# RFM6505B.net
KiCad netlist of a schematic drawn in Altium Designer
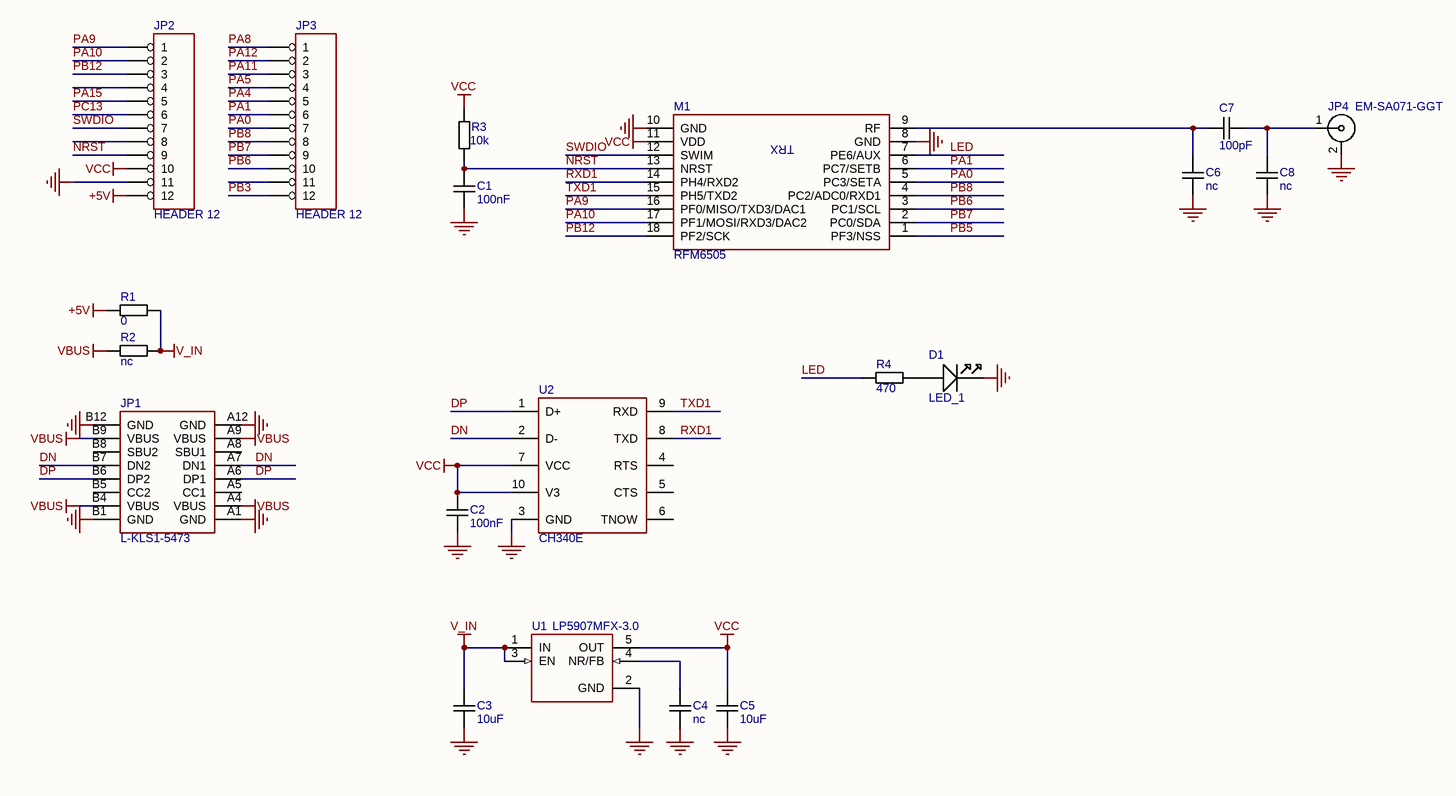
[diagram p0: RFM6505B.SchDoc]

(export (version "E")
  (design (tool "Eeschema 10.0.6"))
  (components
    (comp (ref "C1")
      (value "100nF")
      (footprint "C-0603")
      (fields (field (name "VOLTAGE") "50V"))
      (libsource (lib "Passive") (part "CAPN"))
    )
    (comp (ref "C2")
      (value "100nF")
      (footprint "C-0603")
      (fields (field (name "VOLTAGE") "50V"))
      (libsource (lib "Passive") (part "CAPN"))
    )
    (comp (ref "C3")
      (value "10uF")
      (footprint "C-0805")
      (fields (field (name "VOLTAGE") "50V"))
      (libsource (lib "Passive") (part "CAPN"))
    )
    (comp (ref "C4")
      (value "nc")
      (footprint "C-0603")
      (fields (field (name "VOLTAGE") "50V"))
      (libsource (lib "Passive") (part "CAPN"))
    )
    (comp (ref "C5")
      (value "10uF")
      (footprint "C-0805")
      (fields (field (name "VOLTAGE") "50V"))
      (libsource (lib "Passive") (part "CAPN"))
    )
    (comp (ref "C6")
      (value "nc")
      (footprint "C-0603")
      (fields (field (name "VOLTAGE") "50V"))
      (libsource (lib "Passive") (part "CAPN"))
    )
    (comp (ref "C7")
      (value "100pF")
      (footprint "C-0603")
      (fields (field (name "VOLTAGE") "50V"))
      (libsource (lib "Passive") (part "CAPN"))
    )
    (comp (ref "C8")
      (value "nc")
      (footprint "C-0603")
      (fields (field (name "VOLTAGE") "50V"))
      (libsource (lib "Passive") (part "CAPN"))
    )
    (comp (ref "D1") (value "LED_1") (footprint "LED_0805") (libsource (lib "Diodes") (part "LED_1")))
    (comp (ref "JP1")
      (value "L-KLS1-5473")
      (footprint "USB_C_SMD_SLOT")
      (libsource (lib "Connectors") (part "L-KLS1-5473"))
    )
    (comp (ref "JP2")
      (value "HEADER 12")
      (footprint "PLS1-12")
      (libsource (lib "Connectors") (part "HEADER 12"))
    )
    (comp (ref "JP3")
      (value "HEADER 12")
      (footprint "PLS1-12")
      (libsource (lib "Connectors") (part "HEADER 12"))
    )
    (comp (ref "JP4")
      (value "EM-SA071-GGT")
      (footprint "SMA_F_EDGE")
      (description "SMA Female R/A PCB Mount")
      (libsource (lib "Connectors") (part "SMA"))
    )
    (comp (ref "M1") (value "RFM6505") (footprint "RFM6505") (libsource (lib "RFmodules") (part "RFM6505")))
    (comp (ref "R1") (value "0") (footprint "R-0603") (libsource (lib "Passive") (part "RES")))
    (comp (ref "R2") (value "nc") (footprint "R-0603") (libsource (lib "Passive") (part "RES")))
    (comp (ref "R3") (value "10k") (footprint "R-0603") (libsource (lib "") (part "RES_1")))
    (comp (ref "R4") (value "470") (footprint "R-0603") (libsource (lib "") (part "RES_2")))
    (comp (ref "U1")
      (value "LP5907MFX-3.0")
      (footprint "SOT-23-5")
      (description "250mA Low-Dropout Regulator")
      (libsource (lib "ICs") (part "LP5907"))
    )
    (comp (ref "U2") (value "CH340E") (footprint "MSOP-10") (libsource (lib "ICs") (part "CH340E")))
  )
  (nets
    (net (code "1") (name "+5V") (class "Default")
      (node (ref "JP2") (pin "12") (pinfunction "12_12") (pintype "passive"))
      (node (ref "R1") (pin "1") (pinfunction "1_1") (pintype "passive"))
    )
    (net (code "2") (name "/DN") (class "Default")
      (node (ref "JP1") (pin "A7") (pinfunction "DN1_A7") (pintype "passive"))
      (node (ref "JP1") (pin "B7") (pinfunction "DN2_B7") (pintype "passive"))
      (node (ref "U2") (pin "2") (pinfunction "D-_2") (pintype "passive"))
    )
    (net (code "3") (name "/DP") (class "Default")
      (node (ref "JP1") (pin "A6") (pinfunction "DP1_A6") (pintype "passive"))
      (node (ref "JP1") (pin "B6") (pinfunction "DP2_B6") (pintype "passive"))
      (node (ref "U2") (pin "1") (pinfunction "D+_1") (pintype "passive"))
    )
    (net (code "4") (name "/LED") (class "Default")
      (node (ref "M1") (pin "7") (pinfunction "PE6/AUX_7") (pintype "passive"))
      (node (ref "R4") (pin "2") (pinfunction "2_2") (pintype "passive"))
    )
    (net (code "5") (name "/NRST") (class "Default")
      (node (ref "C1") (pin "2") (pinfunction "2_2") (pintype "passive"))
      (node (ref "JP2") (pin "9") (pinfunction "9_9") (pintype "passive"))
      (node (ref "M1") (pin "13") (pinfunction "NRST_13") (pintype "passive"))
      (node (ref "R3") (pin "1") (pinfunction "1_1") (pintype "passive"))
    )
    (net (code "6") (name "/PA0") (class "Default")
      (node (ref "JP3") (pin "7") (pinfunction "7_7") (pintype "passive"))
      (node (ref "M1") (pin "5") (pinfunction "PC3/SETA_5") (pintype "passive"))
    )
    (net (code "7") (name "/PA1") (class "Default")
      (node (ref "JP3") (pin "6") (pinfunction "6_6") (pintype "passive"))
      (node (ref "M1") (pin "6") (pinfunction "PC7/SETB_6") (pintype "passive"))
    )
    (net (code "8") (name "/PA4") (class "Default")
      (node (ref "JP3") (pin "5") (pinfunction "5_5") (pintype "passive"))
    )
    (net (code "9") (name "/PA5") (class "Default")
      (node (ref "JP3") (pin "4") (pinfunction "4_4") (pintype "passive"))
    )
    (net (code "10") (name "/PA8") (class "Default")
      (node (ref "JP3") (pin "1") (pinfunction "1_1") (pintype "passive"))
    )
    (net (code "11") (name "/PA9") (class "Default")
      (node (ref "JP2") (pin "1") (pinfunction "1_1") (pintype "passive"))
      (node (ref "M1") (pin "16") (pinfunction "PF0/MISO/TXD3/DAC1_16") (pintype "passive"))
    )
    (net (code "12") (name "/PA10") (class "Default")
      (node (ref "JP2") (pin "2") (pinfunction "2_2") (pintype "passive"))
      (node (ref "M1") (pin "17") (pinfunction "PF1/MOSI/RXD3/DAC2_17") (pintype "passive"))
    )
    (net (code "13") (name "/PA11") (class "Default")
      (node (ref "JP3") (pin "3") (pinfunction "3_3") (pintype "passive"))
    )
    (net (code "14") (name "/PA12") (class "Default")
      (node (ref "JP3") (pin "2") (pinfunction "2_2") (pintype "passive"))
    )
    (net (code "15") (name "/PA15") (class "Default")
      (node (ref "JP2") (pin "5") (pinfunction "5_5") (pintype "passive"))
    )
    (net (code "16") (name "/PB3") (class "Default")
      (node (ref "JP3") (pin "12") (pinfunction "12_12") (pintype "passive"))
    )
    (net (code "17") (name "/PB5") (class "Default")
      (node (ref "M1") (pin "1") (pinfunction "PF3/NSS_1") (pintype "passive"))
    )
    (net (code "18") (name "/PB6") (class "Default")
      (node (ref "JP3") (pin "10") (pinfunction "10_10") (pintype "passive"))
      (node (ref "M1") (pin "3") (pinfunction "PC1/SCL_3") (pintype "passive"))
    )
    (net (code "19") (name "/PB7") (class "Default")
      (node (ref "JP3") (pin "9") (pinfunction "9_9") (pintype "passive"))
      (node (ref "M1") (pin "2") (pinfunction "PC0/SDA_2") (pintype "passive"))
    )
    (net (code "20") (name "/PB8") (class "Default")
      (node (ref "JP3") (pin "8") (pinfunction "8_8") (pintype "passive"))
      (node (ref "M1") (pin "4") (pinfunction "PC2/ADC0/RXD1_4") (pintype "passive"))
    )
    (net (code "21") (name "/PB12") (class "Default")
      (node (ref "JP2") (pin "3") (pinfunction "3_3") (pintype "passive"))
      (node (ref "M1") (pin "18") (pinfunction "PF2/SCK_18") (pintype "passive"))
    )
    (net (code "22") (name "/PC13") (class "Default")
      (node (ref "JP2") (pin "6") (pinfunction "6_6") (pintype "passive"))
    )
    (net (code "23") (name "/RXD1") (class "Default")
      (node (ref "M1") (pin "14") (pinfunction "PH4/RXD2_14") (pintype "passive"))
      (node (ref "U2") (pin "8") (pinfunction "TXD_8") (pintype "passive"))
    )
    (net (code "24") (name "/SWDIO") (class "Default")
      (node (ref "JP2") (pin "7") (pinfunction "7_7") (pintype "passive"))
      (node (ref "M1") (pin "12") (pinfunction "SWIM_12") (pintype "passive"))
    )
    (net (code "25") (name "/TXD1") (class "Default")
      (node (ref "M1") (pin "15") (pinfunction "PH5/TXD2_15") (pintype "passive"))
      (node (ref "U2") (pin "9") (pinfunction "RXD_9") (pintype "passive"))
    )
    (net (code "26") (name "GND") (class "Default")
      (node (ref "C1") (pin "1") (pinfunction "1_1") (pintype "passive"))
      (node (ref "C2") (pin "1") (pinfunction "1_1") (pintype "passive"))
      (node (ref "C3") (pin "2") (pinfunction "2_2") (pintype "passive"))
      (node (ref "C4") (pin "2") (pinfunction "2_2") (pintype "passive"))
      (node (ref "C5") (pin "2") (pinfunction "2_2") (pintype "passive"))
      (node (ref "C6") (pin "1") (pinfunction "1_1") (pintype "passive"))
      (node (ref "C8") (pin "1") (pinfunction "1_1") (pintype "passive"))
      (node (ref "D1") (pin "K") (pinfunction "CATHODE_K") (pintype "passive"))
      (node (ref "JP1") (pin "A1") (pinfunction "GND_A1") (pintype "passive"))
      (node (ref "JP1") (pin "A12") (pinfunction "GND_A12") (pintype "passive"))
      (node (ref "JP1") (pin "B1") (pinfunction "GND_B1") (pintype "passive"))
      (node (ref "JP1") (pin "B12") (pinfunction "GND_B12") (pintype "passive"))
      (node (ref "JP2") (pin "11") (pinfunction "11_11") (pintype "passive"))
      (node (ref "JP4") (pin "2") (pinfunction "2_2") (pintype "passive"))
      (node (ref "M1") (pin "10") (pinfunction "GND_10") (pintype "passive"))
      (node (ref "M1") (pin "8") (pinfunction "GND_8") (pintype "passive"))
      (node (ref "U1") (pin "2") (pinfunction "GND_2") (pintype "power_in"))
      (node (ref "U2") (pin "3") (pinfunction "GND_3") (pintype "passive"))
    )
    (net (code "27") (name "Net-(C7-Pad2)") (class "Default")
      (node (ref "C7") (pin "2") (pinfunction "2_2") (pintype "passive"))
      (node (ref "C8") (pin "2") (pinfunction "2_2") (pintype "passive"))
      (node (ref "JP4") (pin "1") (pinfunction "1_1") (pintype "passive"))
    )
    (net (code "28") (name "Net-(D1-ANODE)") (class "Default")
      (node (ref "D1") (pin "A") (pinfunction "ANODE_A") (pintype "passive"))
      (node (ref "R4") (pin "1") (pinfunction "1_1") (pintype "passive"))
    )
    (net (code "29") (name "Net-(M1-RF)") (class "Default")
      (node (ref "C6") (pin "2") (pinfunction "2_2") (pintype "passive"))
      (node (ref "C7") (pin "1") (pinfunction "1_1") (pintype "passive"))
      (node (ref "M1") (pin "9") (pinfunction "RF_9") (pintype "passive"))
    )
    (net (code "30") (name "Net-(U1-NR{slash}FB)") (class "Default")
      (node (ref "C4") (pin "1") (pinfunction "1_1") (pintype "passive"))
      (node (ref "U1") (pin "4") (pinfunction "NR/FB_4") (pintype "input"))
    )
    (net (code "31") (name "VBUS") (class "Default")
      (node (ref "JP1") (pin "A4") (pinfunction "VBUS_A4") (pintype "passive"))
      (node (ref "JP1") (pin "A9") (pinfunction "VBUS_A9") (pintype "passive"))
      (node (ref "JP1") (pin "B4") (pinfunction "VBUS_B4") (pintype "passive"))
      (node (ref "JP1") (pin "B9") (pinfunction "VBUS_B9") (pintype "passive"))
      (node (ref "R2") (pin "1") (pinfunction "1_1") (pintype "passive"))
    )
    (net (code "32") (name "VCC") (class "Default")
      (node (ref "C2") (pin "2") (pinfunction "2_2") (pintype "passive"))
      (node (ref "C5") (pin "1") (pinfunction "1_1") (pintype "passive"))
      (node (ref "JP2") (pin "10") (pinfunction "10_10") (pintype "passive"))
      (node (ref "M1") (pin "11") (pinfunction "VDD_11") (pintype "passive"))
      (node (ref "R3") (pin "2") (pinfunction "2_2") (pintype "passive"))
      (node (ref "U1") (pin "5") (pinfunction "OUT_5") (pintype "power_in"))
      (node (ref "U2") (pin "10") (pinfunction "V3_10") (pintype "passive"))
      (node (ref "U2") (pin "7") (pinfunction "VCC_7") (pintype "passive"))
    )
    (net (code "33") (name "VSS") (class "Default")
      (node (ref "JP1") (pin "17") (pinfunction "VSS_17") (pintype "power_in"))
    )
    (net (code "34") (name "V_IN") (class "Default")
      (node (ref "C3") (pin "1") (pinfunction "1_1") (pintype "passive"))
      (node (ref "R1") (pin "2") (pinfunction "2_2") (pintype "passive"))
      (node (ref "R2") (pin "2") (pinfunction "2_2") (pintype "passive"))
      (node (ref "U1") (pin "1") (pinfunction "IN_1") (pintype "power_in"))
      (node (ref "U1") (pin "3") (pinfunction "EN_3") (pintype "input"))
    )
    (net (code "35") (name "unconnected-(JP1-CC1-PadA5)") (class "Default")
      (node (ref "JP1") (pin "A5") (pinfunction "CC1_A5") (pintype "passive"))
    )
    (net (code "36") (name "unconnected-(JP1-CC2-PadB5)") (class "Default")
      (node (ref "JP1") (pin "B5") (pinfunction "CC2_B5") (pintype "passive"))
    )
    (net (code "37") (name "unconnected-(JP1-SBU1-PadA8)") (class "Default")
      (node (ref "JP1") (pin "A8") (pinfunction "SBU1_A8") (pintype "passive"))
    )
    (net (code "38") (name "unconnected-(JP1-SBU2-PadB8)") (class "Default")
      (node (ref "JP1") (pin "B8") (pinfunction "SBU2_B8") (pintype "passive"))
    )
    (net (code "39") (name "unconnected-(JP2-Pad4)") (class "Default")
      (node (ref "JP2") (pin "4") (pinfunction "4_4") (pintype "passive"))
    )
    (net (code "40") (name "unconnected-(JP2-Pad8)") (class "Default")
      (node (ref "JP2") (pin "8") (pinfunction "8_8") (pintype "passive"))
    )
    (net (code "41") (name "unconnected-(JP3-Pad11)") (class "Default")
      (node (ref "JP3") (pin "11") (pinfunction "11_11") (pintype "passive"))
    )
    (net (code "42") (name "unconnected-(U2-CTS-Pad5)") (class "Default")
      (node (ref "U2") (pin "5") (pinfunction "CTS_5") (pintype "passive"))
    )
    (net (code "43") (name "unconnected-(U2-RTS-Pad4)") (class "Default")
      (node (ref "U2") (pin "4") (pinfunction "RTS_4") (pintype "passive"))
    )
    (net (code "44") (name "unconnected-(U2-TNOW-Pad6)") (class "Default")
      (node (ref "U2") (pin "6") (pinfunction "TNOW_6") (pintype "passive"))
    )
  )
)
